# LC_LPF6.net
KiCad netlist of a schematic drawn in Altium Designer
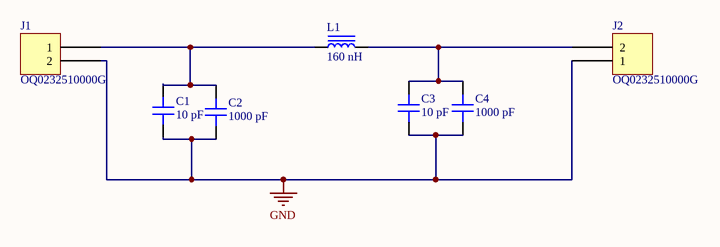
[diagram p0: LC_LPF6.SchDoc]

(export (version "E")
  (design (tool "Eeschema 10.0.6"))
  (components
    (comp (ref "C1")
      (value "10 pF")
      (footprint "CAP 0603_1608")
      (description "CAP CER 10PF 100V C0G/NPO 0603")
      (fields (field (name "PART NUMBER") "AC0603JRNPO0BN100") (field (name "MANUFACTURER") "Yageo"))
      (libsource (lib "Celestial Altium Library - altium_library") (part "Capacitor"))
    )
    (comp (ref "C2")
      (value "1000 pF")
      (footprint "CAP 0603_1608")
      (description "CAP CER 1000PF 100V X7R 0603")
      (fields
        (field (name "PART NUMBER") "GCD188R72A102KA01D")
        (field (name "MANUFACTURER") "Murata Electronics")
      )
      (libsource (lib "Celestial Altium Library - altium_library") (part "Capacitor"))
    )
    (comp (ref "C3")
      (value "10 pF")
      (footprint "CAP 0603_1608")
      (description "CAP CER 10PF 100V C0G/NPO 0603")
      (fields (field (name "PART NUMBER") "AC0603JRNPO0BN100") (field (name "MANUFACTURER") "Yageo"))
      (libsource (lib "Celestial Altium Library - altium_library") (part "Capacitor"))
    )
    (comp (ref "C4")
      (value "1000 pF")
      (footprint "CAP 0603_1608")
      (description "CAP CER 1000PF 100V X7R 0603")
      (fields
        (field (name "PART NUMBER") "GCD188R72A102KA01D")
        (field (name "MANUFACTURER") "Murata Electronics")
      )
      (libsource (lib "Celestial Altium Library - altium_library") (part "Capacitor"))
    )
    (comp (ref "J1")
      (value "OQ0232510000G")
      (footprint "FCI 06-381-2PIN")
      (description "TERM BLOCK HDR 2POS 90DEG 3.81MM")
      (fields (field (name "MANUFACTURER") "Amphenol Anytek"))
      (libsource (lib "Celestial Altium Library - altium_library") (part "2 Pin"))
    )
    (comp (ref "J2")
      (value "OQ0232510000G")
      (footprint "FCI 06-381-2PIN")
      (description "TERM BLOCK HDR 2POS 90DEG 3.81MM")
      (fields (field (name "MANUFACTURER") "Amphenol Anytek"))
      (libsource (lib "") (part "2 Pin_1"))
    )
    (comp (ref "L1")
      (value "160 nH")
      (footprint "IND 0402_1005 RF WW")
      (description "FIXED IND 160NH 480MA 330MOHM SM")
      (fields
        (field (name "PART NUMBER") "LQW15CNR16J00D")
        (field (name "MANUFACTURER") "Murata Electronics")
      )
      (libsource (lib "Celestial Altium Library - altium_library") (part "Inductor"))
    )
  )
  (nets
    (net (code "1") (name "GND") (class "Default")
      (node (ref "C1") (pin "1") (pinfunction "1_1") (pintype "passive"))
      (node (ref "C2") (pin "2") (pinfunction "2_2") (pintype "passive"))
      (node (ref "C3") (pin "1") (pinfunction "1_1") (pintype "passive"))
      (node (ref "C4") (pin "2") (pinfunction "2_2") (pintype "passive"))
      (node (ref "J1") (pin "2") (pinfunction "2_2") (pintype "passive"))
      (node (ref "J2") (pin "1") (pinfunction "1_1") (pintype "passive"))
    )
    (net (code "2") (name "Net-(C1-Pad2)") (class "Default")
      (node (ref "C1") (pin "2") (pinfunction "2_2") (pintype "passive"))
      (node (ref "C2") (pin "1") (pinfunction "1_1") (pintype "passive"))
      (node (ref "J1") (pin "1") (pinfunction "1_1") (pintype "passive"))
      (node (ref "L1") (pin "1") (pinfunction "1_1") (pintype "passive"))
    )
    (net (code "3") (name "Net-(C3-Pad2)") (class "Default")
      (node (ref "C3") (pin "2") (pinfunction "2_2") (pintype "passive"))
      (node (ref "C4") (pin "1") (pinfunction "1_1") (pintype "passive"))
      (node (ref "J2") (pin "2") (pinfunction "2_2") (pintype "passive"))
      (node (ref "L1") (pin "2") (pinfunction "2_2") (pintype "passive"))
    )
  )
)
